# Main_schematic.net
KiCad netlist of a schematic drawn in Altium Designer
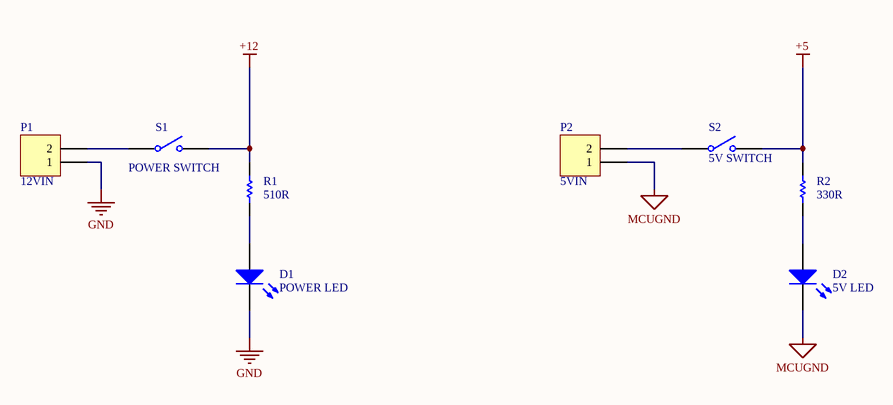
[diagram p0: Main_schematic.SchDoc]

(export (version "E")
  (design (tool "Eeschema 10.0.6"))
  (components
    (comp (ref "D1")
      (value "POWER LED")
      (footprint "LED-1")
      (description "Typical RED GaAs LED")
      (fields (field (name "PUBLISHER") "Altium Limited"))
      (libsource (lib "Miscellaneous Devices") (part "LED1"))
    )
    (comp (ref "D2")
      (value "5V LED")
      (footprint "LED-1")
      (description "Typical RED GaAs LED")
      (fields (field (name "PUBLISHER") "Altium Limited"))
      (libsource (lib "Miscellaneous Devices") (part "LED1"))
    )
    (comp (ref "P1")
      (value "12VIN")
      (footprint "HDR1X2")
      (description "Header, 2-Pin")
      (fields (field (name "PUBLISHER") "Altium Limited"))
      (libsource (lib "Miscellaneous Connectors") (part "Header 2"))
    )
    (comp (ref "P2")
      (value "5VIN")
      (footprint "HDR1X2")
      (description "Header, 2-Pin")
      (fields (field (name "PUBLISHER") "Altium Limited"))
      (libsource (lib "Miscellaneous Connectors") (part "Header 2"))
    )
    (comp (ref "R1")
      (value "510R")
      (footprint "AXIAL-0.3")
      (description "Resistor")
      (fields (field (name "Comment") "Res1") (field (name "PUBLISHER") "Altium Limited"))
      (libsource (lib "Miscellaneous Devices") (part "Res1"))
    )
    (comp (ref "R2")
      (value "330R")
      (footprint "AXIAL-0.3")
      (description "Resistor")
      (fields (field (name "Comment") "Res1") (field (name "PUBLISHER") "Altium Limited"))
      (libsource (lib "Miscellaneous Devices") (part "Res1"))
    )
    (comp (ref "S1")
      (value "POWER SWITCH")
      (footprint "SPST-2")
      (description "Single-Pole, Single-Throw Switch")
      (fields (field (name "PUBLISHER") "Altium Limited"))
      (libsource (lib "Miscellaneous Devices") (part "SW-SPST"))
    )
    (comp (ref "S2")
      (value "5V SWITCH")
      (footprint "SPST-2")
      (description "Single-Pole, Single-Throw Switch")
      (fields (field (name "PUBLISHER") "Altium Limited"))
      (libsource (lib "Miscellaneous Devices") (part "SW-SPST"))
    )
  )
  (nets
    (net (code "1") (name "+5") (class "Default")
      (node (ref "R2") (pin "2") (pinfunction "2_2") (pintype "passive"))
      (node (ref "S2") (pin "2") (pinfunction "NO_2") (pintype "passive"))
    )
    (net (code "2") (name "+12") (class "Default")
      (node (ref "R1") (pin "2") (pinfunction "2_2") (pintype "passive"))
      (node (ref "S1") (pin "2") (pinfunction "NO_2") (pintype "passive"))
    )
    (net (code "3") (name "GND") (class "Default")
      (node (ref "D1") (pin "2") (pinfunction "K_2") (pintype "passive"))
      (node (ref "P1") (pin "1") (pinfunction "1_1") (pintype "passive"))
    )
    (net (code "4") (name "MCUGND") (class "Default")
      (node (ref "D2") (pin "2") (pinfunction "K_2") (pintype "passive"))
      (node (ref "P2") (pin "1") (pinfunction "1_1") (pintype "passive"))
    )
    (net (code "5") (name "Net-(D1-A)") (class "Default")
      (node (ref "D1") (pin "1") (pinfunction "A_1") (pintype "passive"))
      (node (ref "R1") (pin "1") (pinfunction "1_1") (pintype "passive"))
    )
    (net (code "6") (name "Net-(D2-A)") (class "Default")
      (node (ref "D2") (pin "1") (pinfunction "A_1") (pintype "passive"))
      (node (ref "R2") (pin "1") (pinfunction "1_1") (pintype "passive"))
    )
    (net (code "7") (name "Net-(S1-COMMON)") (class "Default")
      (node (ref "P1") (pin "2") (pinfunction "2_2") (pintype "passive"))
      (node (ref "S1") (pin "1") (pinfunction "COMMON_1") (pintype "passive"))
    )
    (net (code "8") (name "Net-(S2-COMMON)") (class "Default")
      (node (ref "P2") (pin "2") (pinfunction "2_2") (pintype "passive"))
      (node (ref "S2") (pin "1") (pinfunction "COMMON_1") (pintype "passive"))
    )
  )
)
